# w6_echo_plus.net
KiCad netlist of a schematic drawn in EAGLE
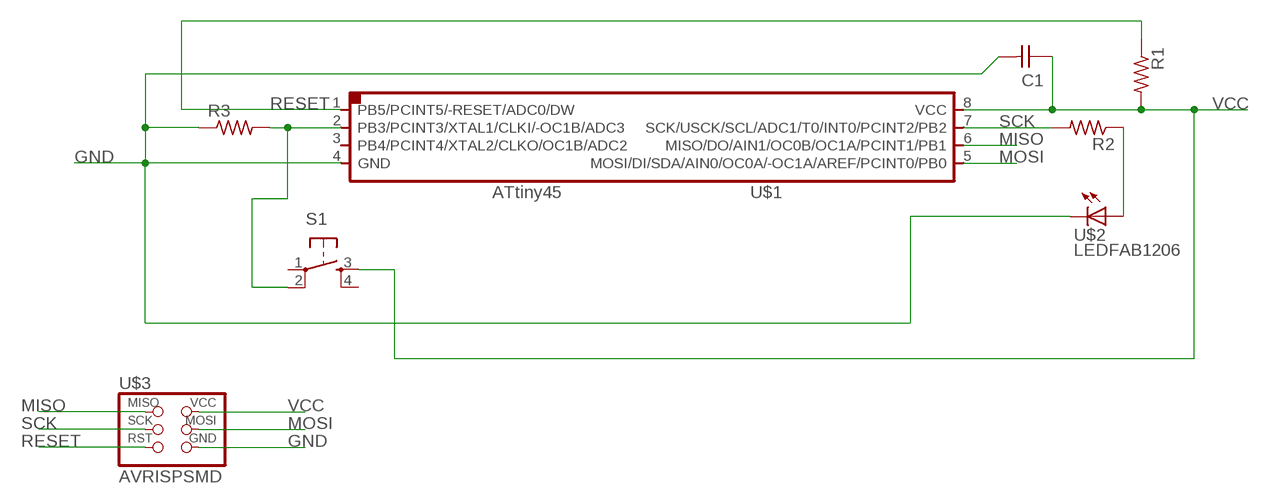
[diagram p0: schematic, sheet 1]

(export (version "E")
  (design (tool "Eeschema 10.0.6"))
  (components
    (comp (ref "C1")
      (value "CAP-UNPOLARIZEDFAB")
      (footprint "eagle-import:C1206FAB")
      (libsource (lib "eagle-import") (part "CAP-UNPOLARIZEDFAB"))
    )
    (comp (ref "R1")
      (value "RES-US1206FAB")
      (footprint "eagle-import:R1206FAB")
      (libsource (lib "eagle-import") (part "RES-US1206FAB"))
    )
    (comp (ref "R2")
      (value "RES-US1206FAB")
      (footprint "eagle-import:R1206FAB")
      (libsource (lib "eagle-import") (part "RES-US1206FAB"))
    )
    (comp (ref "R3")
      (value "RES-US1206FAB")
      (footprint "eagle-import:R1206FAB")
      (libsource (lib "eagle-import") (part "RES-US1206FAB"))
    )
    (comp (ref "S1")
      (value "6MM_SWITCH6MM_SWITCH")
      (footprint "eagle-import:6MM_SWITCH")
      (libsource (lib "eagle-import") (part "6MM_SWITCH6MM_SWITCH"))
    )
    (comp (ref "U$1")
      (value "ATTINY45SI")
      (footprint "eagle-import:SOIC8")
      (libsource (lib "eagle-import") (part "ATTINY45SI"))
    )
    (comp (ref "U$2")
      (value "LEDFAB1206")
      (footprint "eagle-import:LED1206FAB")
      (libsource (lib "eagle-import") (part "LEDFAB1206"))
    )
    (comp (ref "U$3")
      (value "AVRISPSMD")
      (footprint "eagle-import:2X03SMD")
      (libsource (lib "eagle-import") (part "AVRISPSMD"))
    )
  )
  (nets
    (net (code "1") (name "/GND") (class "Default")
      (node (ref "C1") (pin "2") (pinfunction "2_2") (pintype "passive"))
      (node (ref "R3") (pin "1") (pinfunction "1_1") (pintype "passive"))
      (node (ref "U$1") (pin "4") (pinfunction "GND_4") (pintype "bidirectional"))
      (node (ref "U$2") (pin "2") (pinfunction "C_2") (pintype "passive"))
      (node (ref "U$3") (pin "6") (pinfunction "GND_6") (pintype "passive"))
    )
    (net (code "2") (name "/MISO") (class "Default")
      (node (ref "U$1") (pin "6") (pinfunction "MISO/DO/AIN1/OC0B/OC1A/PCINT1/PB1_6") (pintype "bidirectional"))
      (node (ref "U$3") (pin "1") (pinfunction "MISO_1") (pintype "passive"))
    )
    (net (code "3") (name "/MOSI") (class "Default")
      (node (ref "U$1") (pin "5") (pinfunction "MOSI/DI/SDA/AIN0/OC0A/-OC1A/AREF/PCINT0/PB0_5") (pintype "bidirectional"))
      (node (ref "U$3") (pin "4") (pinfunction "MOSI_4") (pintype "passive"))
    )
    (net (code "4") (name "/RESET") (class "Default")
      (node (ref "R1") (pin "1") (pinfunction "1_1") (pintype "passive"))
      (node (ref "U$1") (pin "1") (pinfunction "PB5/PCINT5/-RESET/ADC0/DW_1") (pintype "bidirectional"))
      (node (ref "U$3") (pin "5") (pinfunction "RST_5") (pintype "passive"))
    )
    (net (code "5") (name "/SCK") (class "Default")
      (node (ref "R2") (pin "2") (pinfunction "2_2") (pintype "passive"))
      (node (ref "U$1") (pin "7") (pinfunction "SCK/USCK/SCL/ADC1/T0/INT0/PCINT2/PB2_7") (pintype "bidirectional"))
      (node (ref "U$3") (pin "3") (pinfunction "SCK_3") (pintype "passive"))
    )
    (net (code "6") (name "/VCC") (class "Default")
      (node (ref "C1") (pin "1") (pinfunction "1_1") (pintype "passive"))
      (node (ref "R1") (pin "2") (pinfunction "2_2") (pintype "passive"))
      (node (ref "S1") (pin "3") (pinfunction "S_3") (pintype "passive"))
      (node (ref "U$1") (pin "8") (pinfunction "VCC_8") (pintype "bidirectional"))
      (node (ref "U$3") (pin "2") (pinfunction "VCC_2") (pintype "passive"))
    )
    (net (code "7") (name "Net-(S1-P1)") (class "Default")
      (node (ref "R3") (pin "2") (pinfunction "2_2") (pintype "passive"))
      (node (ref "S1") (pin "2") (pinfunction "P1_2") (pintype "passive"))
      (node (ref "U$1") (pin "2") (pinfunction "PB3/PCINT3/XTAL1/CLKI/-OC1B/ADC3_2") (pintype "bidirectional"))
    )
    (net (code "8") (name "Net-(U$2-A)") (class "Default")
      (node (ref "R2") (pin "1") (pinfunction "1_1") (pintype "passive"))
      (node (ref "U$2") (pin "1") (pinfunction "A_1") (pintype "passive"))
    )
    (net (code "9") (name "unconnected-(S1-P-Pad1)") (class "Default")
      (node (ref "S1") (pin "1") (pinfunction "P_1") (pintype "passive"))
    )
    (net (code "10") (name "unconnected-(S1-S1-Pad4)") (class "Default")
      (node (ref "S1") (pin "4") (pinfunction "S1_4") (pintype "passive"))
    )
    (net (code "11") (name "unconnected-(U$1-PB4{slash}PCINT4{slash}XTAL2{slash}CLKO{slash}OC1B{slash}ADC2-Pad3)") (class "Default")
      (node (ref "U$1") (pin "3") (pinfunction "PB4/PCINT4/XTAL2/CLKO/OC1B/ADC2_3") (pintype "bidirectional"))
    )
  )
)
